# SOIC20-TSSOP20_v1_0.net
KiCad netlist of a schematic drawn in EAGLE
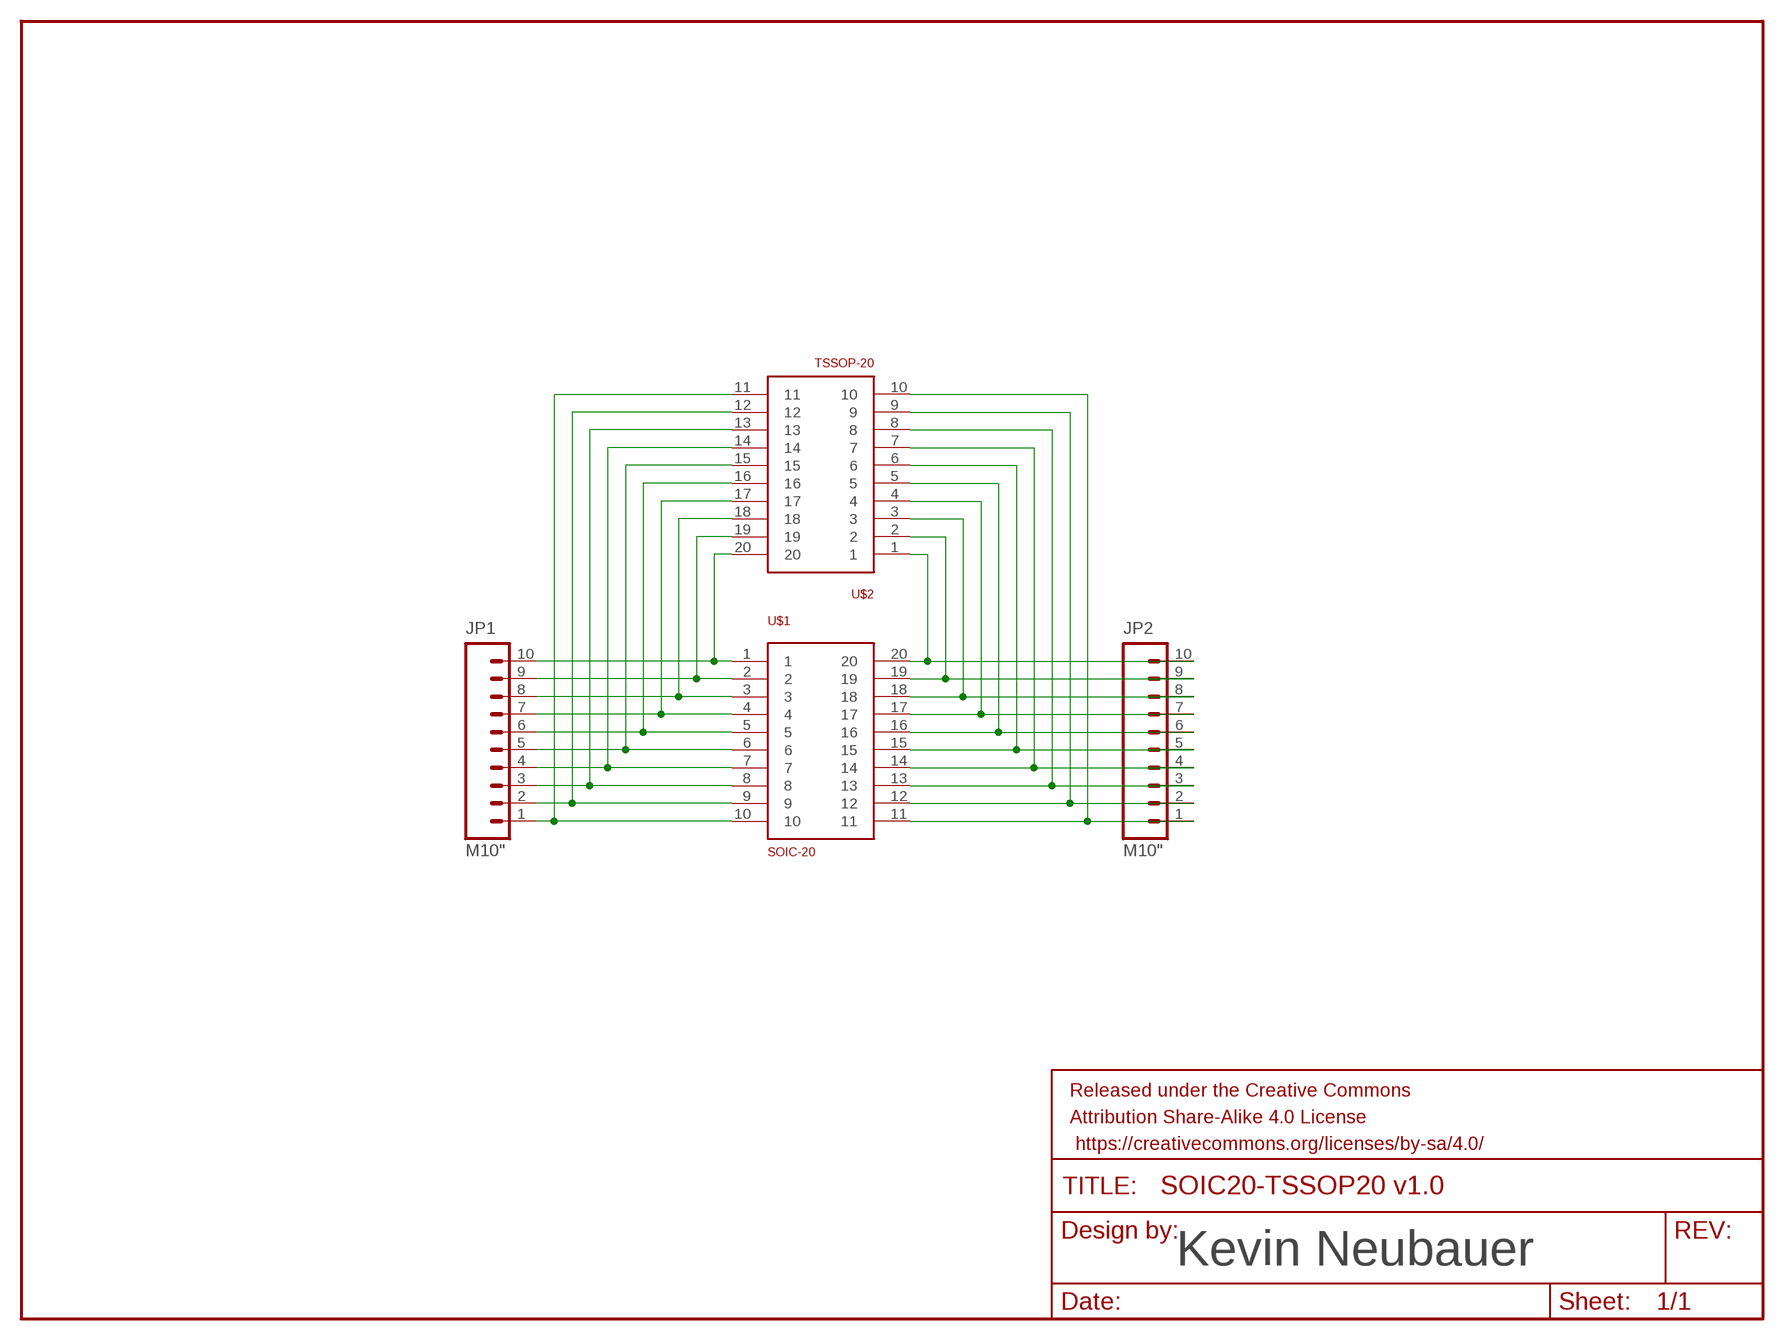
[diagram p0: schematic, sheet 1]

(export (version "E")
  (design (tool "Eeschema 10.0.6"))
  (components
    (comp (ref "FRAME1")
      (value "FRAME-LETTER")
      (footprint "eagle-import:CREATIVE_COMMONS")
      (libsource (lib "eagle-import") (part "FRAME-LETTER"))
    )
    (comp (ref "JP1")
      (value "M10\"")
      (footprint "eagle-import:1X10")
      (libsource (lib "eagle-import") (part "M10{dblquote}"))
    )
    (comp (ref "JP2")
      (value "M10\"")
      (footprint "eagle-import:1X10")
      (libsource (lib "eagle-import") (part "M10{dblquote}"))
    )
    (comp (ref "U$1")
      (value "SOIC-20")
      (footprint "eagle-import:SOIC-20")
      (libsource (lib "eagle-import") (part "SOIC-20"))
    )
    (comp (ref "U$2")
      (value "TSSOP-20")
      (footprint "eagle-import:TSSOP20")
      (libsource (lib "eagle-import") (part "TSSOP-20"))
    )
  )
  (nets
    (net (code "1") (name "Net-(JP1-Pad1)") (class "Default")
      (node (ref "JP1") (pin "1") (pinfunction "1_1") (pintype "passive"))
      (node (ref "U$1") (pin "10") (pinfunction "10_10") (pintype "bidirectional"))
      (node (ref "U$2") (pin "11") (pinfunction "11_11") (pintype "bidirectional"))
    )
    (net (code "2") (name "Net-(JP1-Pad2)") (class "Default")
      (node (ref "JP1") (pin "2") (pinfunction "2_2") (pintype "passive"))
      (node (ref "U$1") (pin "9") (pinfunction "9_9") (pintype "bidirectional"))
      (node (ref "U$2") (pin "12") (pinfunction "12_12") (pintype "bidirectional"))
    )
    (net (code "3") (name "Net-(JP1-Pad3)") (class "Default")
      (node (ref "JP1") (pin "3") (pinfunction "3_3") (pintype "passive"))
      (node (ref "U$1") (pin "8") (pinfunction "8_8") (pintype "bidirectional"))
      (node (ref "U$2") (pin "13") (pinfunction "13_13") (pintype "bidirectional"))
    )
    (net (code "4") (name "Net-(JP1-Pad4)") (class "Default")
      (node (ref "JP1") (pin "4") (pinfunction "4_4") (pintype "passive"))
      (node (ref "U$1") (pin "7") (pinfunction "7_7") (pintype "bidirectional"))
      (node (ref "U$2") (pin "14") (pinfunction "14_14") (pintype "bidirectional"))
    )
    (net (code "5") (name "Net-(JP1-Pad5)") (class "Default")
      (node (ref "JP1") (pin "5") (pinfunction "5_5") (pintype "passive"))
      (node (ref "U$1") (pin "6") (pinfunction "6_6") (pintype "bidirectional"))
      (node (ref "U$2") (pin "15") (pinfunction "15_15") (pintype "bidirectional"))
    )
    (net (code "6") (name "Net-(JP1-Pad6)") (class "Default")
      (node (ref "JP1") (pin "6") (pinfunction "6_6") (pintype "passive"))
      (node (ref "U$1") (pin "5") (pinfunction "5_5") (pintype "bidirectional"))
      (node (ref "U$2") (pin "16") (pinfunction "16_16") (pintype "bidirectional"))
    )
    (net (code "7") (name "Net-(JP1-Pad7)") (class "Default")
      (node (ref "JP1") (pin "7") (pinfunction "7_7") (pintype "passive"))
      (node (ref "U$1") (pin "4") (pinfunction "4_4") (pintype "bidirectional"))
      (node (ref "U$2") (pin "17") (pinfunction "17_17") (pintype "bidirectional"))
    )
    (net (code "8") (name "Net-(JP1-Pad8)") (class "Default")
      (node (ref "JP1") (pin "8") (pinfunction "8_8") (pintype "passive"))
      (node (ref "U$1") (pin "3") (pinfunction "3_3") (pintype "bidirectional"))
      (node (ref "U$2") (pin "18") (pinfunction "18_18") (pintype "bidirectional"))
    )
    (net (code "9") (name "Net-(JP1-Pad9)") (class "Default")
      (node (ref "JP1") (pin "9") (pinfunction "9_9") (pintype "passive"))
      (node (ref "U$1") (pin "2") (pinfunction "2_2") (pintype "bidirectional"))
      (node (ref "U$2") (pin "19") (pinfunction "19_19") (pintype "bidirectional"))
    )
    (net (code "10") (name "Net-(JP1-Pad10)") (class "Default")
      (node (ref "JP1") (pin "10") (pinfunction "10_10") (pintype "passive"))
      (node (ref "U$1") (pin "1") (pinfunction "1_1") (pintype "bidirectional"))
      (node (ref "U$2") (pin "20") (pinfunction "20_20") (pintype "bidirectional"))
    )
    (net (code "11") (name "Net-(JP2-Pad1)") (class "Default")
      (node (ref "JP2") (pin "1") (pinfunction "1_1") (pintype "passive"))
      (node (ref "U$1") (pin "11") (pinfunction "11_11") (pintype "bidirectional"))
      (node (ref "U$2") (pin "10") (pinfunction "10_10") (pintype "bidirectional"))
    )
    (net (code "12") (name "Net-(JP2-Pad2)") (class "Default")
      (node (ref "JP2") (pin "2") (pinfunction "2_2") (pintype "passive"))
      (node (ref "U$1") (pin "12") (pinfunction "12_12") (pintype "bidirectional"))
      (node (ref "U$2") (pin "9") (pinfunction "9_9") (pintype "bidirectional"))
    )
    (net (code "13") (name "Net-(JP2-Pad3)") (class "Default")
      (node (ref "JP2") (pin "3") (pinfunction "3_3") (pintype "passive"))
      (node (ref "U$1") (pin "13") (pinfunction "13_13") (pintype "bidirectional"))
      (node (ref "U$2") (pin "8") (pinfunction "8_8") (pintype "bidirectional"))
    )
    (net (code "14") (name "Net-(JP2-Pad4)") (class "Default")
      (node (ref "JP2") (pin "4") (pinfunction "4_4") (pintype "passive"))
      (node (ref "U$1") (pin "14") (pinfunction "14_14") (pintype "bidirectional"))
      (node (ref "U$2") (pin "7") (pinfunction "7_7") (pintype "bidirectional"))
    )
    (net (code "15") (name "Net-(JP2-Pad5)") (class "Default")
      (node (ref "JP2") (pin "5") (pinfunction "5_5") (pintype "passive"))
      (node (ref "U$1") (pin "15") (pinfunction "15_15") (pintype "bidirectional"))
      (node (ref "U$2") (pin "6") (pinfunction "6_6") (pintype "bidirectional"))
    )
    (net (code "16") (name "Net-(JP2-Pad6)") (class "Default")
      (node (ref "JP2") (pin "6") (pinfunction "6_6") (pintype "passive"))
      (node (ref "U$1") (pin "16") (pinfunction "16_16") (pintype "bidirectional"))
      (node (ref "U$2") (pin "5") (pinfunction "5_5") (pintype "bidirectional"))
    )
    (net (code "17") (name "Net-(JP2-Pad7)") (class "Default")
      (node (ref "JP2") (pin "7") (pinfunction "7_7") (pintype "passive"))
      (node (ref "U$1") (pin "17") (pinfunction "17_17") (pintype "bidirectional"))
      (node (ref "U$2") (pin "4") (pinfunction "4_4") (pintype "bidirectional"))
    )
    (net (code "18") (name "Net-(JP2-Pad8)") (class "Default")
      (node (ref "JP2") (pin "8") (pinfunction "8_8") (pintype "passive"))
      (node (ref "U$1") (pin "18") (pinfunction "18_18") (pintype "bidirectional"))
      (node (ref "U$2") (pin "3") (pinfunction "3_3") (pintype "bidirectional"))
    )
    (net (code "19") (name "Net-(JP2-Pad9)") (class "Default")
      (node (ref "JP2") (pin "9") (pinfunction "9_9") (pintype "passive"))
      (node (ref "U$1") (pin "19") (pinfunction "19_19") (pintype "bidirectional"))
      (node (ref "U$2") (pin "2") (pinfunction "2_2") (pintype "bidirectional"))
    )
    (net (code "20") (name "Net-(JP2-Pad10)") (class "Default")
      (node (ref "JP2") (pin "10") (pinfunction "10_10") (pintype "passive"))
      (node (ref "U$1") (pin "20") (pinfunction "20_20") (pintype "bidirectional"))
      (node (ref "U$2") (pin "1") (pinfunction "1_1") (pintype "bidirectional"))
    )
  )
)
